# exp4_2020-11-30_18-58-26.net
KiCad netlist of a schematic drawn in EasyEDA
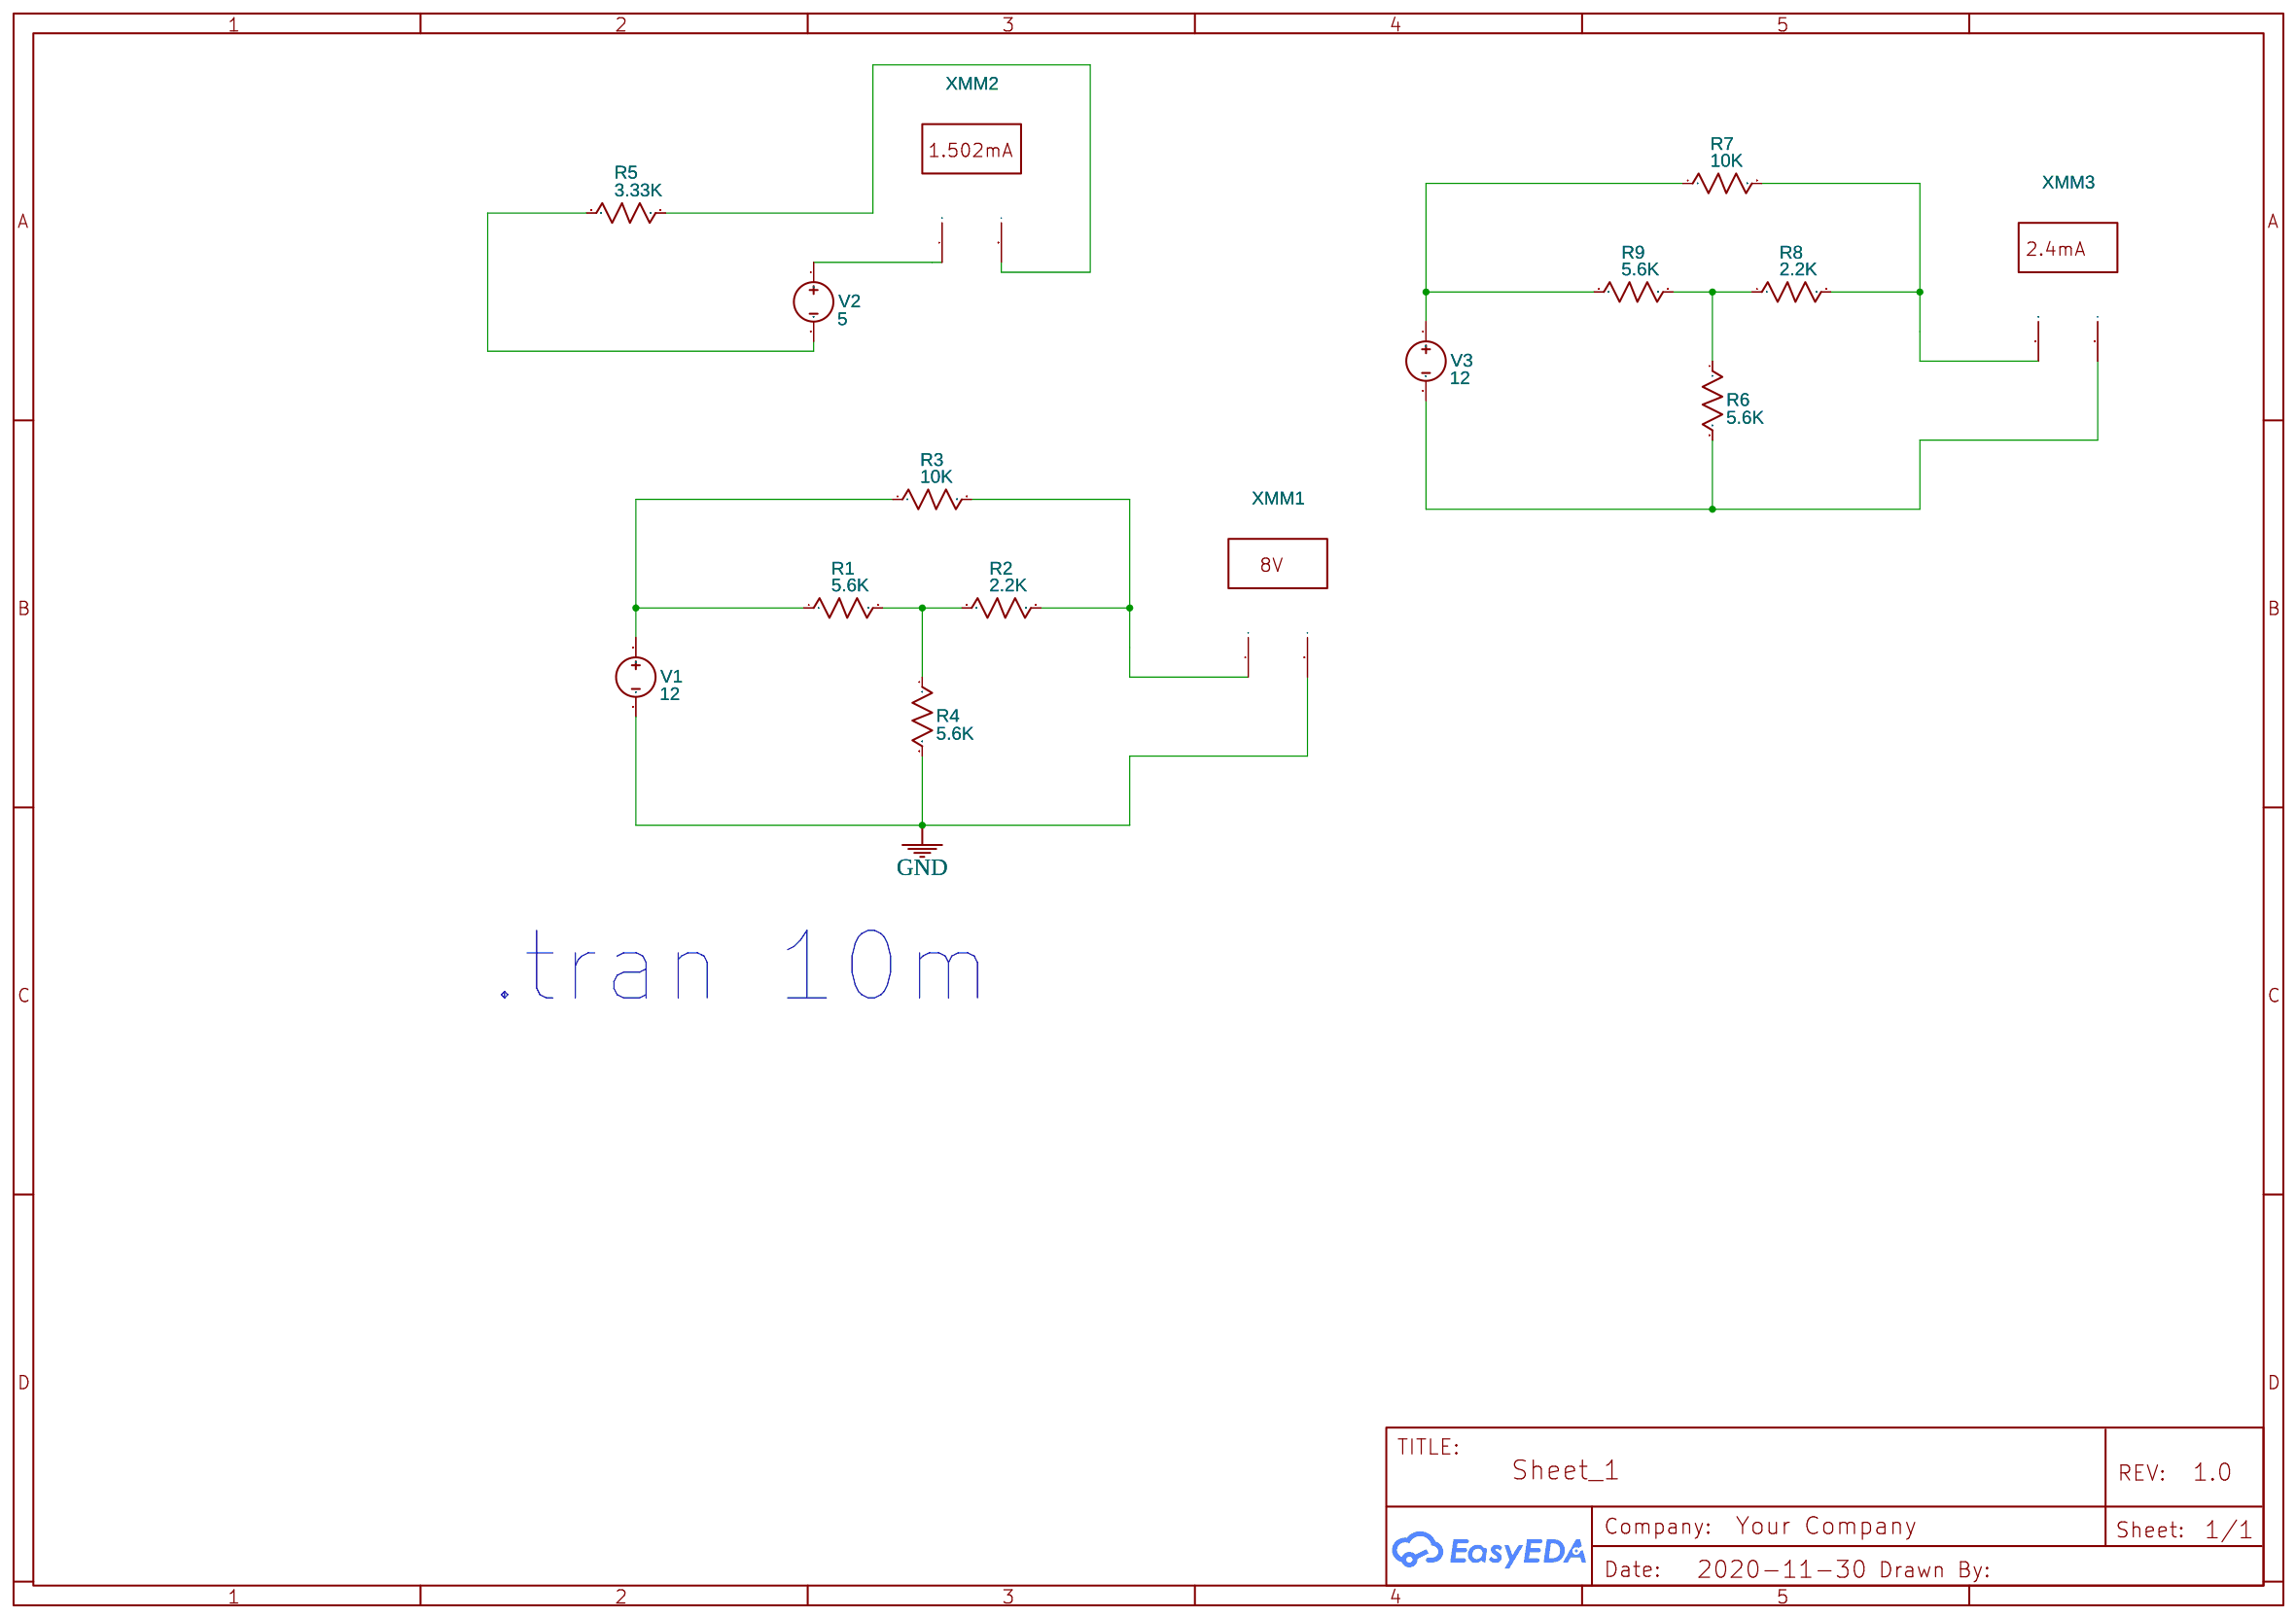
[diagram p0: schematic sheet]

(export (version "E")
  (design (tool "Eeschema 10.0.6"))
  (components
    (comp (ref "R1") (value "5.6K") (libsource (lib "") (part "Resistor_US")))
    (comp (ref "R2") (value "2.2K") (libsource (lib "") (part "Resistor_US")))
    (comp (ref "R3") (value "10K") (libsource (lib "") (part "Resistor_US")))
    (comp (ref "R4") (value "5.6K") (libsource (lib "") (part "Resistor_US_1")))
    (comp (ref "R5") (value "3.33K") (libsource (lib "") (part "Resistor_US")))
    (comp (ref "R6") (value "5.6K") (libsource (lib "") (part "Resistor_US_1")))
    (comp (ref "R7") (value "10K") (libsource (lib "") (part "Resistor_US")))
    (comp (ref "R8") (value "2.2K") (libsource (lib "") (part "Resistor_US")))
    (comp (ref "R9") (value "5.6K") (libsource (lib "") (part "Resistor_US")))
    (comp (ref "V1") (value "12") (libsource (lib "") (part "VDC")))
    (comp (ref "V2") (value "5") (libsource (lib "") (part "VDC")))
    (comp (ref "V3") (value "12") (libsource (lib "") (part "VDC")))
    (comp (ref "XMM1") (value "Multimeter") (libsource (lib "") (part "MULTIMETER_1")))
    (comp (ref "XMM2") (value "Multimeter") (libsource (lib "") (part "MULTIMETER_2")))
    (comp (ref "XMM3") (value "Multimeter") (libsource (lib "") (part "MULTIMETER")))
  )
  (nets
    (net (code "1") (name "GND") (class "Default")
      (node (ref "R4") (pin "2") (pinfunction "2_2") (pintype "unspecified"))
      (node (ref "V1") (pin "2") (pinfunction "2_2") (pintype "unspecified"))
      (node (ref "XMM1") (pin "2") (pinfunction "I_2") (pintype "unspecified"))
    )
    (net (code "2") (name "Net-(R1-Pad1)") (class "Default")
      (node (ref "R1") (pin "1") (pinfunction "1_1") (pintype "unspecified"))
      (node (ref "R3") (pin "1") (pinfunction "1_1") (pintype "unspecified"))
      (node (ref "V1") (pin "1") (pinfunction "1_1") (pintype "unspecified"))
    )
    (net (code "3") (name "Net-(R1-Pad2)") (class "Default")
      (node (ref "R1") (pin "2") (pinfunction "2_2") (pintype "unspecified"))
      (node (ref "R2") (pin "1") (pinfunction "1_1") (pintype "unspecified"))
      (node (ref "R4") (pin "1") (pinfunction "1_1") (pintype "unspecified"))
    )
    (net (code "4") (name "Net-(R5-Pad1)") (class "Default")
      (node (ref "R5") (pin "1") (pinfunction "1_1") (pintype "unspecified"))
      (node (ref "V2") (pin "2") (pinfunction "2_2") (pintype "unspecified"))
    )
    (net (code "5") (name "Net-(R6-Pad1)") (class "Default")
      (node (ref "R6") (pin "1") (pinfunction "1_1") (pintype "unspecified"))
      (node (ref "R8") (pin "1") (pinfunction "1_1") (pintype "unspecified"))
      (node (ref "R9") (pin "2") (pinfunction "2_2") (pintype "unspecified"))
    )
    (net (code "6") (name "Net-(R7-Pad1)") (class "Default")
      (node (ref "R7") (pin "1") (pinfunction "1_1") (pintype "unspecified"))
      (node (ref "R9") (pin "1") (pinfunction "1_1") (pintype "unspecified"))
      (node (ref "V3") (pin "1") (pinfunction "1_1") (pintype "unspecified"))
    )
    (net (code "7") (name "Net-(XMM1-+)") (class "Default")
      (node (ref "R2") (pin "2") (pinfunction "2_2") (pintype "unspecified"))
      (node (ref "R3") (pin "2") (pinfunction "2_2") (pintype "unspecified"))
      (node (ref "XMM1") (pin "1") (pinfunction "+_1") (pintype "unspecified"))
    )
    (net (code "8") (name "Net-(XMM2-+)") (class "Default")
      (node (ref "V2") (pin "1") (pinfunction "1_1") (pintype "unspecified"))
      (node (ref "XMM2") (pin "1") (pinfunction "+_1") (pintype "unspecified"))
    )
    (net (code "9") (name "Net-(XMM2-I)") (class "Default")
      (node (ref "R5") (pin "2") (pinfunction "2_2") (pintype "unspecified"))
      (node (ref "XMM2") (pin "2") (pinfunction "I_2") (pintype "unspecified"))
    )
    (net (code "10") (name "Net-(XMM3-+)") (class "Default")
      (node (ref "R7") (pin "2") (pinfunction "2_2") (pintype "unspecified"))
      (node (ref "R8") (pin "2") (pinfunction "2_2") (pintype "unspecified"))
      (node (ref "XMM3") (pin "1") (pinfunction "+_1") (pintype "unspecified"))
    )
    (net (code "11") (name "Net-(XMM3-I)") (class "Default")
      (node (ref "R6") (pin "2") (pinfunction "2_2") (pintype "unspecified"))
      (node (ref "V3") (pin "2") (pinfunction "2_2") (pintype "unspecified"))
      (node (ref "XMM3") (pin "2") (pinfunction "I_2") (pintype "unspecified"))
    )
  )
)
